# Kentec-pin-relayout.net
KiCad netlist of a schematic drawn in EAGLE
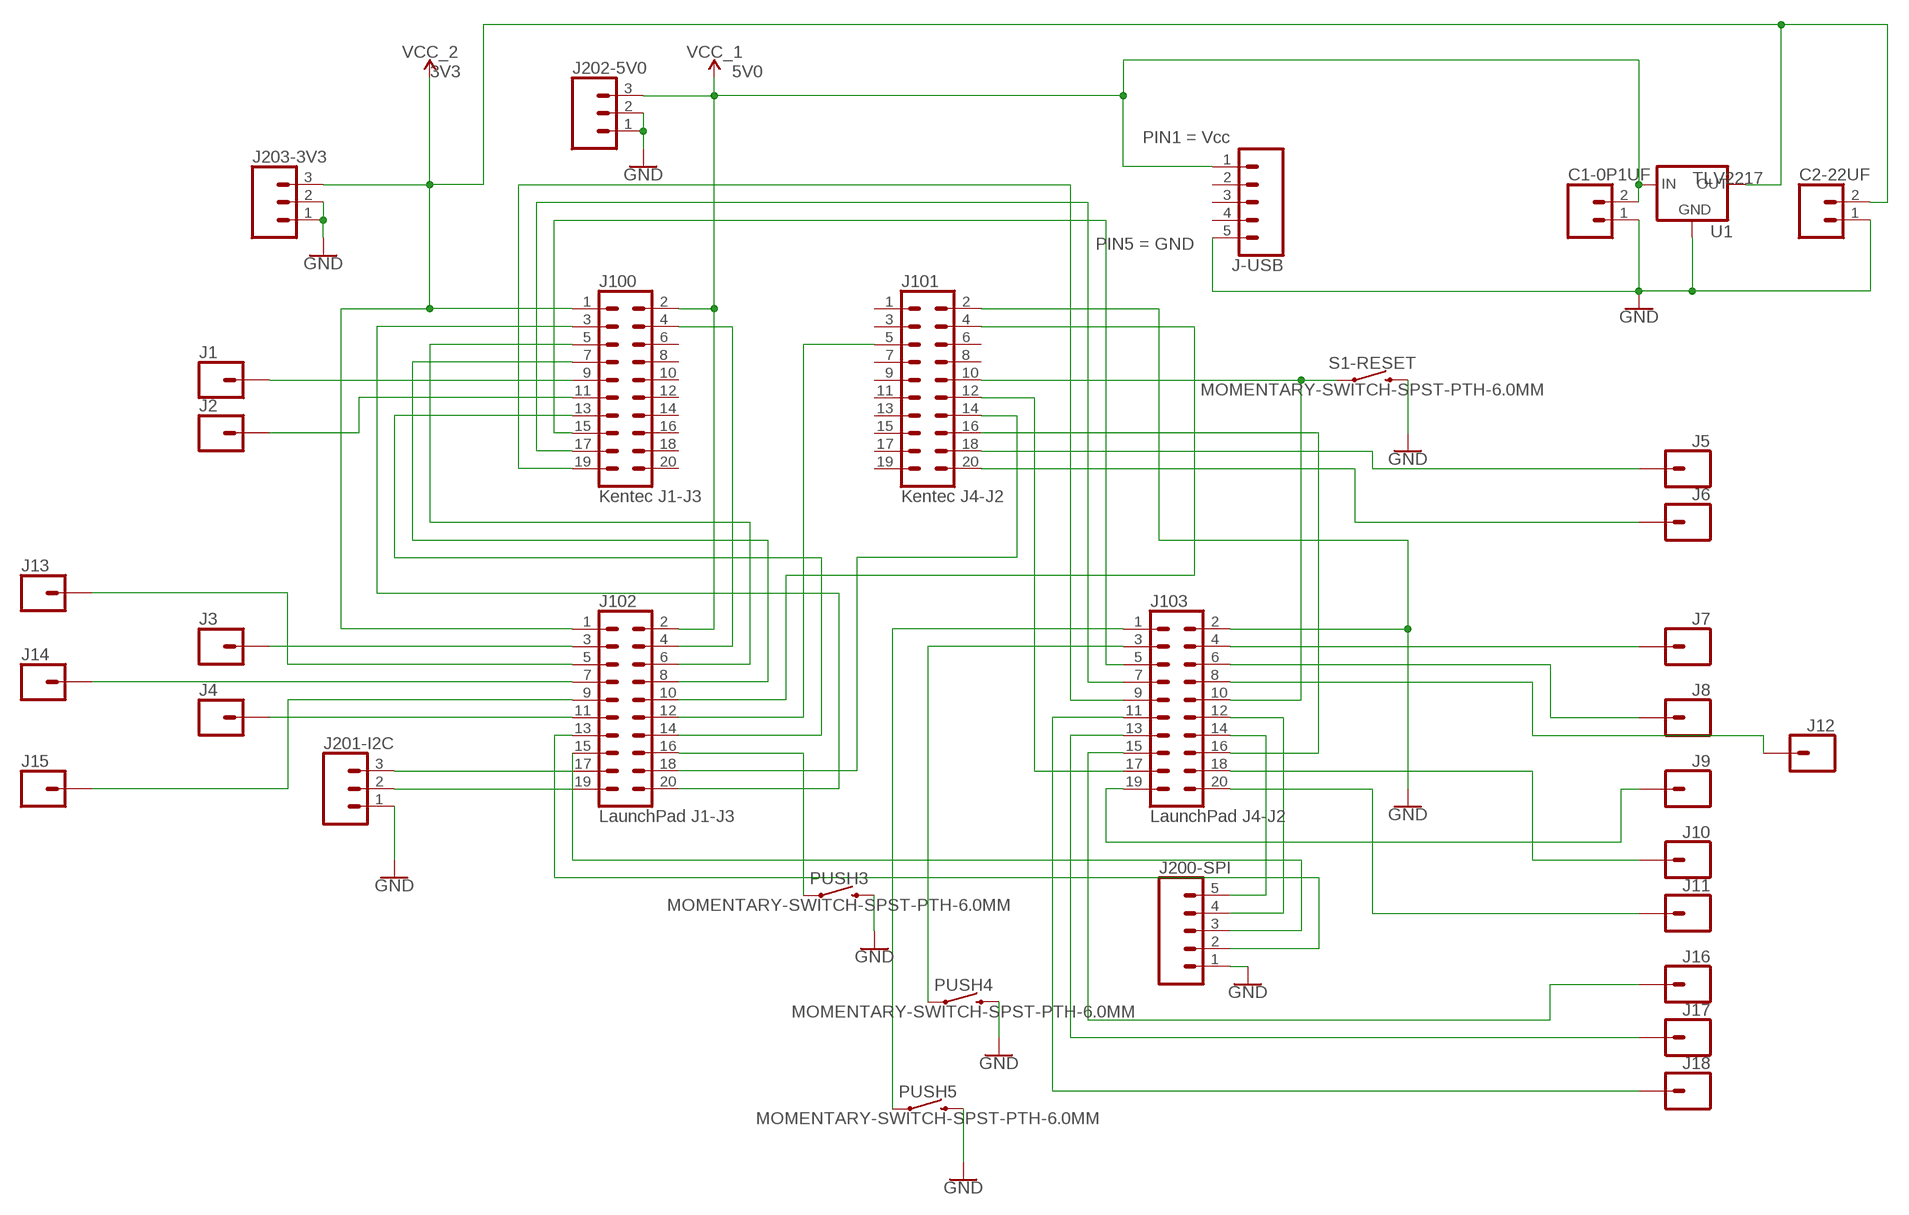
[diagram p0: schematic, sheet 1]

(export (version "E")
  (design (tool "Eeschema 10.0.6"))
  (components
    (comp (ref "C1-0P1UF")
      (value "CONN_02")
      (footprint "eagle-import:1X02")
      (libsource (lib "eagle-import") (part "CONN_02"))
    )
    (comp (ref "C2-22UF")
      (value "CONN_02")
      (footprint "eagle-import:1X02")
      (libsource (lib "eagle-import") (part "CONN_02"))
    )
    (comp (ref "J-USB")
      (value "CONN_05LOCK")
      (footprint "eagle-import:1X05_LOCK")
      (fields (field (name "PIN1") "Vcc") (field (name "PIN5") "GND"))
      (libsource (lib "eagle-import") (part "CONN_05LOCK"))
    )
    (comp (ref "J1")
      (value "CONN_01")
      (footprint "eagle-import:1X01")
      (libsource (lib "eagle-import") (part "CONN_01"))
    )
    (comp (ref "J2")
      (value "CONN_01")
      (footprint "eagle-import:1X01")
      (libsource (lib "eagle-import") (part "CONN_01"))
    )
    (comp (ref "J3")
      (value "CONN_01")
      (footprint "eagle-import:1X01")
      (libsource (lib "eagle-import") (part "CONN_01"))
    )
    (comp (ref "J4")
      (value "CONN_01")
      (footprint "eagle-import:1X01")
      (libsource (lib "eagle-import") (part "CONN_01"))
    )
    (comp (ref "J5")
      (value "CONN_01")
      (footprint "eagle-import:1X01")
      (libsource (lib "eagle-import") (part "CONN_01"))
    )
    (comp (ref "J6")
      (value "CONN_01")
      (footprint "eagle-import:1X01")
      (libsource (lib "eagle-import") (part "CONN_01"))
    )
    (comp (ref "J7")
      (value "CONN_01")
      (footprint "eagle-import:1X01")
      (libsource (lib "eagle-import") (part "CONN_01"))
    )
    (comp (ref "J8")
      (value "CONN_01")
      (footprint "eagle-import:1X01")
      (libsource (lib "eagle-import") (part "CONN_01"))
    )
    (comp (ref "J9")
      (value "CONN_01")
      (footprint "eagle-import:1X01")
      (libsource (lib "eagle-import") (part "CONN_01"))
    )
    (comp (ref "J10")
      (value "CONN_01")
      (footprint "eagle-import:1X01")
      (libsource (lib "eagle-import") (part "CONN_01"))
    )
    (comp (ref "J11")
      (value "CONN_01")
      (footprint "eagle-import:1X01")
      (libsource (lib "eagle-import") (part "CONN_01"))
    )
    (comp (ref "J12")
      (value "CONN_01")
      (footprint "eagle-import:1X01")
      (libsource (lib "eagle-import") (part "CONN_01"))
    )
    (comp (ref "J13")
      (value "CONN_01")
      (footprint "eagle-import:1X01")
      (libsource (lib "eagle-import") (part "CONN_01"))
    )
    (comp (ref "J14")
      (value "CONN_01")
      (footprint "eagle-import:1X01")
      (libsource (lib "eagle-import") (part "CONN_01"))
    )
    (comp (ref "J15")
      (value "CONN_01")
      (footprint "eagle-import:1X01")
      (libsource (lib "eagle-import") (part "CONN_01"))
    )
    (comp (ref "J16")
      (value "CONN_01")
      (footprint "eagle-import:1X01")
      (libsource (lib "eagle-import") (part "CONN_01"))
    )
    (comp (ref "J17")
      (value "CONN_01")
      (footprint "eagle-import:1X01")
      (libsource (lib "eagle-import") (part "CONN_01"))
    )
    (comp (ref "J18")
      (value "CONN_01")
      (footprint "eagle-import:1X01")
      (libsource (lib "eagle-import") (part "CONN_01"))
    )
    (comp (ref "J100")
      (value "Kentec J1-J3")
      (footprint "eagle-import:2X10_LOCK")
      (libsource (lib "eagle-import") (part "CONN_10X22X10_LOCK"))
    )
    (comp (ref "J101")
      (value "Kentec J4-J2")
      (footprint "eagle-import:2X10_LOCK")
      (libsource (lib "eagle-import") (part "CONN_10X22X10_LOCK"))
    )
    (comp (ref "J102")
      (value "LaunchPad J1-J3")
      (footprint "eagle-import:2X10_LOCK")
      (libsource (lib "eagle-import") (part "CONN_10X22X10_LOCK"))
    )
    (comp (ref "J103")
      (value "LaunchPad J4-J2")
      (footprint "eagle-import:2X10_LOCK")
      (libsource (lib "eagle-import") (part "CONN_10X22X10_LOCK"))
    )
    (comp (ref "J200-SPI")
      (value "CONN_05LOCK")
      (footprint "eagle-import:1X05_LOCK")
      (libsource (lib "eagle-import") (part "CONN_05LOCK"))
    )
    (comp (ref "J201-I2C")
      (value "CONN_03LOCK")
      (footprint "eagle-import:1X03_LOCK")
      (libsource (lib "eagle-import") (part "CONN_03LOCK"))
    )
    (comp (ref "J202-5V0")
      (value "CONN_03LOCK")
      (footprint "eagle-import:1X03_LOCK")
      (libsource (lib "eagle-import") (part "CONN_03LOCK"))
    )
    (comp (ref "J203-3V3")
      (value "CONN_03LOCK")
      (footprint "eagle-import:1X03_LOCK")
      (libsource (lib "eagle-import") (part "CONN_03LOCK"))
    )
    (comp (ref "PUSH3")
      (value "MOMENTARY-SWITCH-SPST-PTH-6.0MM")
      (footprint "eagle-import:TACTILE_SWITCH_PTH_6.0MM")
      (libsource (lib "eagle-import") (part "MOMENTARY-SWITCH-SPST-PTH-6.0MM"))
    )
    (comp (ref "PUSH4")
      (value "MOMENTARY-SWITCH-SPST-PTH-6.0MM")
      (footprint "eagle-import:TACTILE_SWITCH_PTH_6.0MM")
      (libsource (lib "eagle-import") (part "MOMENTARY-SWITCH-SPST-PTH-6.0MM"))
    )
    (comp (ref "PUSH5")
      (value "MOMENTARY-SWITCH-SPST-PTH-6.0MM")
      (footprint "eagle-import:TACTILE_SWITCH_PTH_6.0MM")
      (libsource (lib "eagle-import") (part "MOMENTARY-SWITCH-SPST-PTH-6.0MM"))
    )
    (comp (ref "S1-RESET")
      (value "MOMENTARY-SWITCH-SPST-PTH-6.0MM")
      (footprint "eagle-import:TACTILE_SWITCH_PTH_6.0MM")
      (libsource (lib "eagle-import") (part "MOMENTARY-SWITCH-SPST-PTH-6.0MM"))
    )
    (comp (ref "U1")
      (value "V_REG_78XX-TO-220")
      (footprint "eagle-import:TO-220-ALT")
      (libsource (lib "eagle-import") (part "V_REG_78XX-TO-220"))
    )
  )
  (nets
    (net (code "1") (name "GND") (class "Default")
      (node (ref "C1-0P1UF") (pin "1") (pinfunction "1_1") (pintype "passive"))
      (node (ref "C2-22UF") (pin "1") (pinfunction "1_1") (pintype "passive"))
      (node (ref "J-USB") (pin "5") (pinfunction "5_5") (pintype "passive"))
      (node (ref "J101") (pin "2") (pinfunction "2_2") (pintype "passive"))
      (node (ref "J103") (pin "2") (pinfunction "2_2") (pintype "passive"))
      (node (ref "J200-SPI") (pin "1") (pinfunction "1_1") (pintype "passive"))
      (node (ref "J201-I2C") (pin "1") (pinfunction "1_1") (pintype "passive"))
      (node (ref "J202-5V0") (pin "1") (pinfunction "1_1") (pintype "passive"))
      (node (ref "J202-5V0") (pin "2") (pinfunction "2_2") (pintype "passive"))
      (node (ref "J203-3V3") (pin "1") (pinfunction "1_1") (pintype "passive"))
      (node (ref "J203-3V3") (pin "2") (pinfunction "2_2") (pintype "passive"))
      (node (ref "PUSH3") (pin "3") (pinfunction "2_3") (pintype "passive"))
      (node (ref "PUSH4") (pin "3") (pinfunction "2_3") (pintype "passive"))
      (node (ref "PUSH5") (pin "3") (pinfunction "2_3") (pintype "passive"))
      (node (ref "S1-RESET") (pin "3") (pinfunction "2_3") (pintype "passive"))
      (node (ref "U1") (pin "GND") (pinfunction "GND_GND") (pintype "input"))
    )
    (net (code "2") (name "Net-(J1-Pad1)") (class "Default")
      (node (ref "J1") (pin "1") (pinfunction "1_1") (pintype "passive"))
      (node (ref "J100") (pin "9") (pinfunction "9_9") (pintype "passive"))
    )
    (net (code "3") (name "Net-(J10-Pad1)") (class "Default")
      (node (ref "J10") (pin "1") (pinfunction "1_1") (pintype "passive"))
      (node (ref "J103") (pin "18") (pinfunction "18_18") (pintype "passive"))
    )
    (net (code "4") (name "Net-(J100-Pad3)") (class "Default")
      (node (ref "J100") (pin "3") (pinfunction "3_3") (pintype "passive"))
      (node (ref "J102") (pin "20") (pinfunction "20_20") (pintype "passive"))
    )
    (net (code "5") (name "Net-(J100-Pad4)") (class "Default")
      (node (ref "J100") (pin "4") (pinfunction "4_4") (pintype "passive"))
      (node (ref "J102") (pin "4") (pinfunction "4_4") (pintype "passive"))
    )
    (net (code "6") (name "Net-(J100-Pad5)") (class "Default")
      (node (ref "J100") (pin "5") (pinfunction "5_5") (pintype "passive"))
      (node (ref "J102") (pin "6") (pinfunction "6_6") (pintype "passive"))
    )
    (net (code "7") (name "Net-(J100-Pad7)") (class "Default")
      (node (ref "J100") (pin "7") (pinfunction "7_7") (pintype "passive"))
      (node (ref "J102") (pin "8") (pinfunction "8_8") (pintype "passive"))
    )
    (net (code "8") (name "Net-(J100-Pad11)") (class "Default")
      (node (ref "J100") (pin "11") (pinfunction "11_11") (pintype "passive"))
      (node (ref "J2") (pin "1") (pinfunction "1_1") (pintype "passive"))
    )
    (net (code "9") (name "Net-(J100-Pad13)") (class "Default")
      (node (ref "J100") (pin "13") (pinfunction "13_13") (pintype "passive"))
      (node (ref "J102") (pin "14") (pinfunction "14_14") (pintype "passive"))
    )
    (net (code "10") (name "Net-(J100-Pad15)") (class "Default")
      (node (ref "J100") (pin "15") (pinfunction "15_15") (pintype "passive"))
      (node (ref "J103") (pin "5") (pinfunction "5_5") (pintype "passive"))
    )
    (net (code "11") (name "Net-(J100-Pad17)") (class "Default")
      (node (ref "J100") (pin "17") (pinfunction "17_17") (pintype "passive"))
      (node (ref "J103") (pin "7") (pinfunction "7_7") (pintype "passive"))
    )
    (net (code "12") (name "Net-(J100-Pad19)") (class "Default")
      (node (ref "J100") (pin "19") (pinfunction "19_19") (pintype "passive"))
      (node (ref "J103") (pin "9") (pinfunction "9_9") (pintype "passive"))
    )
    (net (code "13") (name "Net-(J101-Pad4)") (class "Default")
      (node (ref "J101") (pin "4") (pinfunction "4_4") (pintype "passive"))
      (node (ref "J102") (pin "10") (pinfunction "10_10") (pintype "passive"))
    )
    (net (code "14") (name "Net-(J101-Pad5)") (class "Default")
      (node (ref "J101") (pin "5") (pinfunction "5_5") (pintype "passive"))
      (node (ref "J102") (pin "12") (pinfunction "12_12") (pintype "passive"))
    )
    (net (code "15") (name "Net-(J101-Pad10)") (class "Default")
      (node (ref "J101") (pin "10") (pinfunction "10_10") (pintype "passive"))
      (node (ref "J103") (pin "10") (pinfunction "10_10") (pintype "passive"))
      (node (ref "S1-RESET") (pin "1") (pinfunction "1_1") (pintype "passive"))
    )
    (net (code "16") (name "Net-(J101-Pad12)") (class "Default")
      (node (ref "J101") (pin "12") (pinfunction "12_12") (pintype "passive"))
      (node (ref "J103") (pin "17") (pinfunction "17_17") (pintype "passive"))
    )
    (net (code "17") (name "Net-(J101-Pad14)") (class "Default")
      (node (ref "J101") (pin "14") (pinfunction "14_14") (pintype "passive"))
      (node (ref "J102") (pin "18") (pinfunction "18_18") (pintype "passive"))
    )
    (net (code "18") (name "Net-(J101-Pad16)") (class "Default")
      (node (ref "J101") (pin "16") (pinfunction "16_16") (pintype "passive"))
      (node (ref "J103") (pin "16") (pinfunction "16_16") (pintype "passive"))
    )
    (net (code "19") (name "Net-(J101-Pad18)") (class "Default")
      (node (ref "J101") (pin "18") (pinfunction "18_18") (pintype "passive"))
      (node (ref "J5") (pin "1") (pinfunction "1_1") (pintype "passive"))
    )
    (net (code "20") (name "Net-(J101-Pad20)") (class "Default")
      (node (ref "J101") (pin "20") (pinfunction "20_20") (pintype "passive"))
      (node (ref "J6") (pin "1") (pinfunction "1_1") (pintype "passive"))
    )
    (net (code "21") (name "Net-(J102-Pad3)") (class "Default")
      (node (ref "J102") (pin "3") (pinfunction "3_3") (pintype "passive"))
      (node (ref "J3") (pin "1") (pinfunction "1_1") (pintype "passive"))
    )
    (net (code "22") (name "Net-(J102-Pad5)") (class "Default")
      (node (ref "J102") (pin "5") (pinfunction "5_5") (pintype "passive"))
      (node (ref "J13") (pin "1") (pinfunction "1_1") (pintype "passive"))
    )
    (net (code "23") (name "Net-(J102-Pad7)") (class "Default")
      (node (ref "J102") (pin "7") (pinfunction "7_7") (pintype "passive"))
      (node (ref "J14") (pin "1") (pinfunction "1_1") (pintype "passive"))
    )
    (net (code "24") (name "Net-(J102-Pad9)") (class "Default")
      (node (ref "J102") (pin "9") (pinfunction "9_9") (pintype "passive"))
      (node (ref "J15") (pin "1") (pinfunction "1_1") (pintype "passive"))
    )
    (net (code "25") (name "Net-(J102-Pad11)") (class "Default")
      (node (ref "J102") (pin "11") (pinfunction "11_11") (pintype "passive"))
      (node (ref "J4") (pin "1") (pinfunction "1_1") (pintype "passive"))
    )
    (net (code "26") (name "Net-(J102-Pad13)") (class "Default")
      (node (ref "J102") (pin "13") (pinfunction "13_13") (pintype "passive"))
      (node (ref "J200-SPI") (pin "2") (pinfunction "2_2") (pintype "passive"))
    )
    (net (code "27") (name "Net-(J102-Pad15)") (class "Default")
      (node (ref "J102") (pin "15") (pinfunction "15_15") (pintype "passive"))
      (node (ref "J200-SPI") (pin "3") (pinfunction "3_3") (pintype "passive"))
    )
    (net (code "28") (name "Net-(J102-Pad16)") (class "Default")
      (node (ref "J102") (pin "16") (pinfunction "16_16") (pintype "passive"))
      (node (ref "PUSH3") (pin "1") (pinfunction "1_1") (pintype "passive"))
    )
    (net (code "29") (name "Net-(J102-Pad17)") (class "Default")
      (node (ref "J102") (pin "17") (pinfunction "17_17") (pintype "passive"))
      (node (ref "J201-I2C") (pin "3") (pinfunction "3_3") (pintype "passive"))
    )
    (net (code "30") (name "Net-(J102-Pad19)") (class "Default")
      (node (ref "J102") (pin "19") (pinfunction "19_19") (pintype "passive"))
      (node (ref "J201-I2C") (pin "2") (pinfunction "2_2") (pintype "passive"))
    )
    (net (code "31") (name "Net-(J103-Pad1)") (class "Default")
      (node (ref "J103") (pin "1") (pinfunction "1_1") (pintype "passive"))
      (node (ref "PUSH5") (pin "1") (pinfunction "1_1") (pintype "passive"))
    )
    (net (code "32") (name "Net-(J103-Pad3)") (class "Default")
      (node (ref "J103") (pin "3") (pinfunction "3_3") (pintype "passive"))
      (node (ref "PUSH4") (pin "1") (pinfunction "1_1") (pintype "passive"))
    )
    (net (code "33") (name "Net-(J103-Pad4)") (class "Default")
      (node (ref "J103") (pin "4") (pinfunction "4_4") (pintype "passive"))
      (node (ref "J7") (pin "1") (pinfunction "1_1") (pintype "passive"))
    )
    (net (code "34") (name "Net-(J103-Pad6)") (class "Default")
      (node (ref "J103") (pin "6") (pinfunction "6_6") (pintype "passive"))
      (node (ref "J8") (pin "1") (pinfunction "1_1") (pintype "passive"))
    )
    (net (code "35") (name "Net-(J103-Pad8)") (class "Default")
      (node (ref "J103") (pin "8") (pinfunction "8_8") (pintype "passive"))
      (node (ref "J12") (pin "1") (pinfunction "1_1") (pintype "passive"))
    )
    (net (code "36") (name "Net-(J103-Pad11)") (class "Default")
      (node (ref "J103") (pin "11") (pinfunction "11_11") (pintype "passive"))
      (node (ref "J18") (pin "1") (pinfunction "1_1") (pintype "passive"))
    )
    (net (code "37") (name "Net-(J103-Pad12)") (class "Default")
      (node (ref "J103") (pin "12") (pinfunction "12_12") (pintype "passive"))
      (node (ref "J200-SPI") (pin "4") (pinfunction "4_4") (pintype "passive"))
    )
    (net (code "38") (name "Net-(J103-Pad13)") (class "Default")
      (node (ref "J103") (pin "13") (pinfunction "13_13") (pintype "passive"))
      (node (ref "J17") (pin "1") (pinfunction "1_1") (pintype "passive"))
    )
    (net (code "39") (name "Net-(J103-Pad14)") (class "Default")
      (node (ref "J103") (pin "14") (pinfunction "14_14") (pintype "passive"))
      (node (ref "J200-SPI") (pin "5") (pinfunction "5_5") (pintype "passive"))
    )
    (net (code "40") (name "Net-(J103-Pad15)") (class "Default")
      (node (ref "J103") (pin "15") (pinfunction "15_15") (pintype "passive"))
      (node (ref "J16") (pin "1") (pinfunction "1_1") (pintype "passive"))
    )
    (net (code "41") (name "Net-(J103-Pad19)") (class "Default")
      (node (ref "J103") (pin "19") (pinfunction "19_19") (pintype "passive"))
      (node (ref "J9") (pin "1") (pinfunction "1_1") (pintype "passive"))
    )
    (net (code "42") (name "Net-(J103-Pad20)") (class "Default")
      (node (ref "J103") (pin "20") (pinfunction "20_20") (pintype "passive"))
      (node (ref "J11") (pin "1") (pinfunction "1_1") (pintype "passive"))
    )
    (net (code "43") (name "VCC_1") (class "Default")
      (node (ref "C1-0P1UF") (pin "2") (pinfunction "2_2") (pintype "passive"))
      (node (ref "J-USB") (pin "1") (pinfunction "1_1") (pintype "passive"))
      (node (ref "J100") (pin "2") (pinfunction "2_2") (pintype "passive"))
      (node (ref "J102") (pin "2") (pinfunction "2_2") (pintype "passive"))
      (node (ref "J202-5V0") (pin "3") (pinfunction "3_3") (pintype "passive"))
      (node (ref "U1") (pin "IN") (pinfunction "IN_IN") (pintype "input"))
    )
    (net (code "44") (name "VCC_2") (class "Default")
      (node (ref "C2-22UF") (pin "2") (pinfunction "2_2") (pintype "passive"))
      (node (ref "J100") (pin "1") (pinfunction "1_1") (pintype "passive"))
      (node (ref "J102") (pin "1") (pinfunction "1_1") (pintype "passive"))
      (node (ref "J203-3V3") (pin "3") (pinfunction "3_3") (pintype "passive"))
      (node (ref "U1") (pin "OUT") (pinfunction "OUT_OUT") (pintype "passive"))
    )
    (net (code "45") (name "unconnected-(J-USB-Pad2)") (class "Default")
      (node (ref "J-USB") (pin "2") (pinfunction "2_2") (pintype "passive"))
    )
    (net (code "46") (name "unconnected-(J-USB-Pad3)") (class "Default")
      (node (ref "J-USB") (pin "3") (pinfunction "3_3") (pintype "passive"))
    )
    (net (code "47") (name "unconnected-(J-USB-Pad4)") (class "Default")
      (node (ref "J-USB") (pin "4") (pinfunction "4_4") (pintype "passive"))
    )
    (net (code "48") (name "unconnected-(J100-Pad6)") (class "Default")
      (node (ref "J100") (pin "6") (pinfunction "6_6") (pintype "passive"))
    )
    (net (code "49") (name "unconnected-(J100-Pad8)") (class "Default")
      (node (ref "J100") (pin "8") (pinfunction "8_8") (pintype "passive"))
    )
    (net (code "50") (name "unconnected-(J100-Pad10)") (class "Default")
      (node (ref "J100") (pin "10") (pinfunction "10_10") (pintype "passive"))
    )
    (net (code "51") (name "unconnected-(J100-Pad12)") (class "Default")
      (node (ref "J100") (pin "12") (pinfunction "12_12") (pintype "passive"))
    )
    (net (code "52") (name "unconnected-(J100-Pad14)") (class "Default")
      (node (ref "J100") (pin "14") (pinfunction "14_14") (pintype "passive"))
    )
    (net (code "53") (name "unconnected-(J100-Pad16)") (class "Default")
      (node (ref "J100") (pin "16") (pinfunction "16_16") (pintype "passive"))
    )
    (net (code "54") (name "unconnected-(J100-Pad18)") (class "Default")
      (node (ref "J100") (pin "18") (pinfunction "18_18") (pintype "passive"))
    )
    (net (code "55") (name "unconnected-(J100-Pad20)") (class "Default")
      (node (ref "J100") (pin "20") (pinfunction "20_20") (pintype "passive"))
    )
    (net (code "56") (name "unconnected-(J101-Pad1)") (class "Default")
      (node (ref "J101") (pin "1") (pinfunction "1_1") (pintype "passive"))
    )
    (net (code "57") (name "unconnected-(J101-Pad3)") (class "Default")
      (node (ref "J101") (pin "3") (pinfunction "3_3") (pintype "passive"))
    )
    (net (code "58") (name "unconnected-(J101-Pad6)") (class "Default")
      (node (ref "J101") (pin "6") (pinfunction "6_6") (pintype "passive"))
    )
    (net (code "59") (name "unconnected-(J101-Pad7)") (class "Default")
      (node (ref "J101") (pin "7") (pinfunction "7_7") (pintype "passive"))
    )
    (net (code "60") (name "unconnected-(J101-Pad8)") (class "Default")
      (node (ref "J101") (pin "8") (pinfunction "8_8") (pintype "passive"))
    )
    (net (code "61") (name "unconnected-(J101-Pad9)") (class "Default")
      (node (ref "J101") (pin "9") (pinfunction "9_9") (pintype "passive"))
    )
    (net (code "62") (name "unconnected-(J101-Pad11)") (class "Default")
      (node (ref "J101") (pin "11") (pinfunction "11_11") (pintype "passive"))
    )
    (net (code "63") (name "unconnected-(J101-Pad13)") (class "Default")
      (node (ref "J101") (pin "13") (pinfunction "13_13") (pintype "passive"))
    )
    (net (code "64") (name "unconnected-(J101-Pad15)") (class "Default")
      (node (ref "J101") (pin "15") (pinfunction "15_15") (pintype "passive"))
    )
    (net (code "65") (name "unconnected-(J101-Pad17)") (class "Default")
      (node (ref "J101") (pin "17") (pinfunction "17_17") (pintype "passive"))
    )
    (net (code "66") (name "unconnected-(J101-Pad19)") (class "Default")
      (node (ref "J101") (pin "19") (pinfunction "19_19") (pintype "passive"))
    )
  )
)
